# CartePuissance.net
KiCad netlist of a schematic drawn in Altium Designer
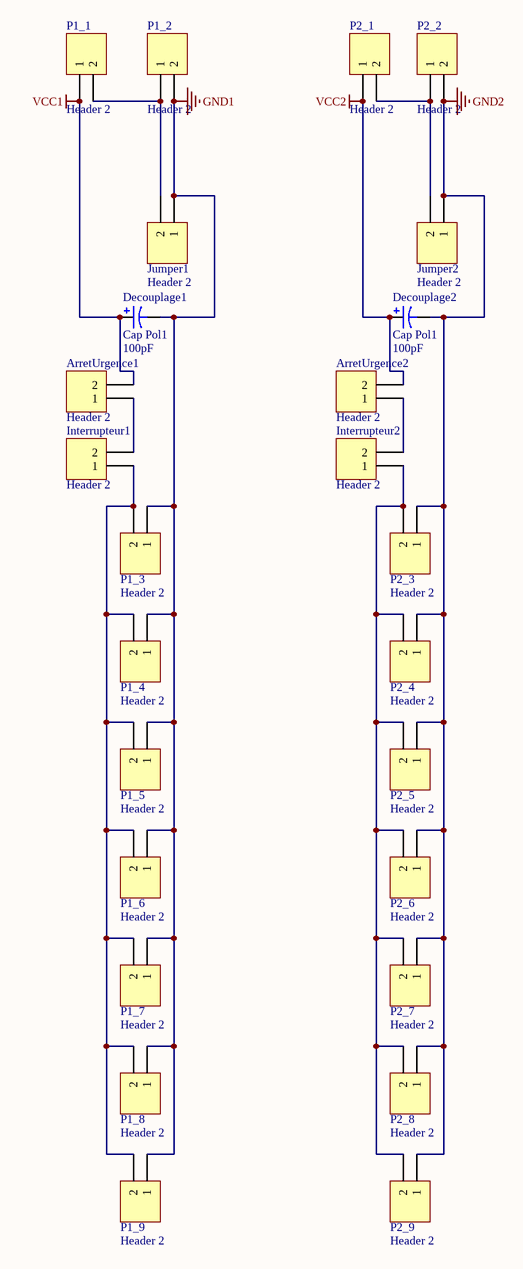
[diagram p0: CartePuissance.SchDoc]

(export (version "E")
  (design (tool "Eeschema 10.0.6"))
  (components
    (comp (ref "ArretUrgence1")
      (value "Header 2")
      (footprint "HDR1X2")
      (description "Header, 2-Pin")
      (fields (field (name "PUBLISHER") "Altium Limited"))
      (libsource (lib "") (part "Header 2_2"))
    )
    (comp (ref "ArretUrgence2")
      (value "Header 2")
      (footprint "HDR1X2")
      (description "Header, 2-Pin")
      (fields (field (name "PUBLISHER") "Altium Limited"))
      (libsource (lib "") (part "Header 2_2"))
    )
    (comp (ref "Decouplage1")
      (value "Cap Pol1")
      (footprint "RB7.6-15")
      (description "Polarized Capacitor (Radial)")
      (fields (field (name "ALTIUM_VALUE") "100pF") (field (name "PUBLISHER") "Altium Limited"))
      (libsource (lib "Miscellaneous Devices") (part "Cap Pol1"))
    )
    (comp (ref "Decouplage2")
      (value "Cap Pol1")
      (footprint "RB7.6-15")
      (description "Polarized Capacitor (Radial)")
      (fields (field (name "ALTIUM_VALUE") "100pF") (field (name "PUBLISHER") "Altium Limited"))
      (libsource (lib "Miscellaneous Devices") (part "Cap Pol1"))
    )
    (comp (ref "Interrupteur1")
      (value "Header 2")
      (footprint "HDR1X2")
      (description "Header, 2-Pin")
      (fields (field (name "PUBLISHER") "Altium Limited"))
      (libsource (lib "") (part "Header 2_2"))
    )
    (comp (ref "Interrupteur2")
      (value "Header 2")
      (footprint "HDR1X2")
      (description "Header, 2-Pin")
      (fields (field (name "PUBLISHER") "Altium Limited"))
      (libsource (lib "") (part "Header 2_2"))
    )
    (comp (ref "Jumper1")
      (value "Header 2")
      (footprint "HDR1X2")
      (description "Header, 2-Pin")
      (fields (field (name "PUBLISHER") "Altium Limited"))
      (libsource (lib "Miscellaneous Connectors") (part "Header 2"))
    )
    (comp (ref "Jumper2")
      (value "Header 2")
      (footprint "HDR1X2")
      (description "Header, 2-Pin")
      (fields (field (name "PUBLISHER") "Altium Limited"))
      (libsource (lib "Miscellaneous Connectors") (part "Header 2"))
    )
    (comp (ref "P1_1")
      (value "Header 2")
      (footprint "HDR1X2")
      (description "Header, 2-Pin")
      (fields (field (name "PUBLISHER") "Altium Limited"))
      (libsource (lib "") (part "Header 2_1"))
    )
    (comp (ref "P1_2")
      (value "Header 2")
      (footprint "HDR1X2")
      (description "Header, 2-Pin")
      (fields (field (name "PUBLISHER") "Altium Limited"))
      (libsource (lib "") (part "Header 2_1"))
    )
    (comp (ref "P1_3")
      (value "Header 2")
      (footprint "HDR1X2")
      (description "Header, 2-Pin")
      (fields (field (name "PUBLISHER") "Altium Limited"))
      (libsource (lib "Miscellaneous Connectors") (part "Header 2"))
    )
    (comp (ref "P1_4")
      (value "Header 2")
      (footprint "HDR1X2")
      (description "Header, 2-Pin")
      (fields (field (name "PUBLISHER") "Altium Limited"))
      (libsource (lib "Miscellaneous Connectors") (part "Header 2"))
    )
    (comp (ref "P1_5")
      (value "Header 2")
      (footprint "HDR1X2")
      (description "Header, 2-Pin")
      (fields (field (name "PUBLISHER") "Altium Limited"))
      (libsource (lib "Miscellaneous Connectors") (part "Header 2"))
    )
    (comp (ref "P1_6")
      (value "Header 2")
      (footprint "HDR1X2")
      (description "Header, 2-Pin")
      (fields (field (name "PUBLISHER") "Altium Limited"))
      (libsource (lib "Miscellaneous Connectors") (part "Header 2"))
    )
    (comp (ref "P1_7")
      (value "Header 2")
      (footprint "HDR1X2")
      (description "Header, 2-Pin")
      (fields (field (name "PUBLISHER") "Altium Limited"))
      (libsource (lib "Miscellaneous Connectors") (part "Header 2"))
    )
    (comp (ref "P1_8")
      (value "Header 2")
      (footprint "HDR1X2")
      (description "Header, 2-Pin")
      (fields (field (name "PUBLISHER") "Altium Limited"))
      (libsource (lib "Miscellaneous Connectors") (part "Header 2"))
    )
    (comp (ref "P1_9")
      (value "Header 2")
      (footprint "HDR1X2")
      (description "Header, 2-Pin")
      (fields (field (name "PUBLISHER") "Altium Limited"))
      (libsource (lib "Miscellaneous Connectors") (part "Header 2"))
    )
    (comp (ref "P2_1")
      (value "Header 2")
      (footprint "HDR1X2")
      (description "Header, 2-Pin")
      (fields (field (name "PUBLISHER") "Altium Limited"))
      (libsource (lib "") (part "Header 2_1"))
    )
    (comp (ref "P2_2")
      (value "Header 2")
      (footprint "HDR1X2")
      (description "Header, 2-Pin")
      (fields (field (name "PUBLISHER") "Altium Limited"))
      (libsource (lib "") (part "Header 2_1"))
    )
    (comp (ref "P2_3")
      (value "Header 2")
      (footprint "HDR1X2")
      (description "Header, 2-Pin")
      (fields (field (name "PUBLISHER") "Altium Limited"))
      (libsource (lib "Miscellaneous Connectors") (part "Header 2"))
    )
    (comp (ref "P2_4")
      (value "Header 2")
      (footprint "HDR1X2")
      (description "Header, 2-Pin")
      (fields (field (name "PUBLISHER") "Altium Limited"))
      (libsource (lib "Miscellaneous Connectors") (part "Header 2"))
    )
    (comp (ref "P2_5")
      (value "Header 2")
      (footprint "HDR1X2")
      (description "Header, 2-Pin")
      (fields (field (name "PUBLISHER") "Altium Limited"))
      (libsource (lib "Miscellaneous Connectors") (part "Header 2"))
    )
    (comp (ref "P2_6")
      (value "Header 2")
      (footprint "HDR1X2")
      (description "Header, 2-Pin")
      (fields (field (name "PUBLISHER") "Altium Limited"))
      (libsource (lib "Miscellaneous Connectors") (part "Header 2"))
    )
    (comp (ref "P2_7")
      (value "Header 2")
      (footprint "HDR1X2")
      (description "Header, 2-Pin")
      (fields (field (name "PUBLISHER") "Altium Limited"))
      (libsource (lib "Miscellaneous Connectors") (part "Header 2"))
    )
    (comp (ref "P2_8")
      (value "Header 2")
      (footprint "HDR1X2")
      (description "Header, 2-Pin")
      (fields (field (name "PUBLISHER") "Altium Limited"))
      (libsource (lib "Miscellaneous Connectors") (part "Header 2"))
    )
    (comp (ref "P2_9")
      (value "Header 2")
      (footprint "HDR1X2")
      (description "Header, 2-Pin")
      (fields (field (name "PUBLISHER") "Altium Limited"))
      (libsource (lib "Miscellaneous Connectors") (part "Header 2"))
    )
  )
  (nets
    (net (code "1") (name "GND1") (class "Default")
      (node (ref "Decouplage1") (pin "2") (pinfunction "2_2") (pintype "passive"))
      (node (ref "Jumper1") (pin "1") (pinfunction "1_1") (pintype "passive"))
      (node (ref "P1_2") (pin "2") (pinfunction "2_2") (pintype "passive"))
      (node (ref "P1_3") (pin "1") (pinfunction "1_1") (pintype "passive"))
      (node (ref "P1_4") (pin "1") (pinfunction "1_1") (pintype "passive"))
      (node (ref "P1_5") (pin "1") (pinfunction "1_1") (pintype "passive"))
      (node (ref "P1_6") (pin "1") (pinfunction "1_1") (pintype "passive"))
      (node (ref "P1_7") (pin "1") (pinfunction "1_1") (pintype "passive"))
      (node (ref "P1_8") (pin "1") (pinfunction "1_1") (pintype "passive"))
      (node (ref "P1_9") (pin "1") (pinfunction "1_1") (pintype "passive"))
    )
    (net (code "2") (name "GND2") (class "Default")
      (node (ref "Decouplage2") (pin "2") (pinfunction "2_2") (pintype "passive"))
      (node (ref "Jumper2") (pin "1") (pinfunction "1_1") (pintype "passive"))
      (node (ref "P2_2") (pin "2") (pinfunction "2_2") (pintype "passive"))
      (node (ref "P2_3") (pin "1") (pinfunction "1_1") (pintype "passive"))
      (node (ref "P2_4") (pin "1") (pinfunction "1_1") (pintype "passive"))
      (node (ref "P2_5") (pin "1") (pinfunction "1_1") (pintype "passive"))
      (node (ref "P2_6") (pin "1") (pinfunction "1_1") (pintype "passive"))
      (node (ref "P2_7") (pin "1") (pinfunction "1_1") (pintype "passive"))
      (node (ref "P2_8") (pin "1") (pinfunction "1_1") (pintype "passive"))
      (node (ref "P2_9") (pin "1") (pinfunction "1_1") (pintype "passive"))
    )
    (net (code "3") (name "Net-(ArretUrgence1-Pad1)") (class "Default")
      (node (ref "ArretUrgence1") (pin "1") (pinfunction "1_1") (pintype "passive"))
      (node (ref "Interrupteur1") (pin "2") (pinfunction "2_2") (pintype "passive"))
    )
    (net (code "4") (name "Net-(ArretUrgence2-Pad1)") (class "Default")
      (node (ref "ArretUrgence2") (pin "1") (pinfunction "1_1") (pintype "passive"))
      (node (ref "Interrupteur2") (pin "2") (pinfunction "2_2") (pintype "passive"))
    )
    (net (code "5") (name "Net-(Interrupteur1-Pad1)") (class "Default")
      (node (ref "Interrupteur1") (pin "1") (pinfunction "1_1") (pintype "passive"))
      (node (ref "P1_3") (pin "2") (pinfunction "2_2") (pintype "passive"))
      (node (ref "P1_4") (pin "2") (pinfunction "2_2") (pintype "passive"))
      (node (ref "P1_5") (pin "2") (pinfunction "2_2") (pintype "passive"))
      (node (ref "P1_6") (pin "2") (pinfunction "2_2") (pintype "passive"))
      (node (ref "P1_7") (pin "2") (pinfunction "2_2") (pintype "passive"))
      (node (ref "P1_8") (pin "2") (pinfunction "2_2") (pintype "passive"))
      (node (ref "P1_9") (pin "2") (pinfunction "2_2") (pintype "passive"))
    )
    (net (code "6") (name "Net-(Interrupteur2-Pad1)") (class "Default")
      (node (ref "Interrupteur2") (pin "1") (pinfunction "1_1") (pintype "passive"))
      (node (ref "P2_3") (pin "2") (pinfunction "2_2") (pintype "passive"))
      (node (ref "P2_4") (pin "2") (pinfunction "2_2") (pintype "passive"))
      (node (ref "P2_5") (pin "2") (pinfunction "2_2") (pintype "passive"))
      (node (ref "P2_6") (pin "2") (pinfunction "2_2") (pintype "passive"))
      (node (ref "P2_7") (pin "2") (pinfunction "2_2") (pintype "passive"))
      (node (ref "P2_8") (pin "2") (pinfunction "2_2") (pintype "passive"))
      (node (ref "P2_9") (pin "2") (pinfunction "2_2") (pintype "passive"))
    )
    (net (code "7") (name "Net-(Jumper1-Pad2)") (class "Default")
      (node (ref "Jumper1") (pin "2") (pinfunction "2_2") (pintype "passive"))
      (node (ref "P1_1") (pin "2") (pinfunction "2_2") (pintype "passive"))
      (node (ref "P1_2") (pin "1") (pinfunction "1_1") (pintype "passive"))
    )
    (net (code "8") (name "Net-(Jumper2-Pad2)") (class "Default")
      (node (ref "Jumper2") (pin "2") (pinfunction "2_2") (pintype "passive"))
      (node (ref "P2_1") (pin "2") (pinfunction "2_2") (pintype "passive"))
      (node (ref "P2_2") (pin "1") (pinfunction "1_1") (pintype "passive"))
    )
    (net (code "9") (name "VCC1") (class "Default")
      (node (ref "ArretUrgence1") (pin "2") (pinfunction "2_2") (pintype "passive"))
      (node (ref "Decouplage1") (pin "1") (pinfunction "1_1") (pintype "passive"))
      (node (ref "P1_1") (pin "1") (pinfunction "1_1") (pintype "passive"))
    )
    (net (code "10") (name "VCC2") (class "Default")
      (node (ref "ArretUrgence2") (pin "2") (pinfunction "2_2") (pintype "passive"))
      (node (ref "Decouplage2") (pin "1") (pinfunction "1_1") (pintype "passive"))
      (node (ref "P2_1") (pin "1") (pinfunction "1_1") (pintype "passive"))
    )
  )
)
